# 3_STM32F103_Debugger.net
KiCad netlist of a schematic drawn in Altium Designer
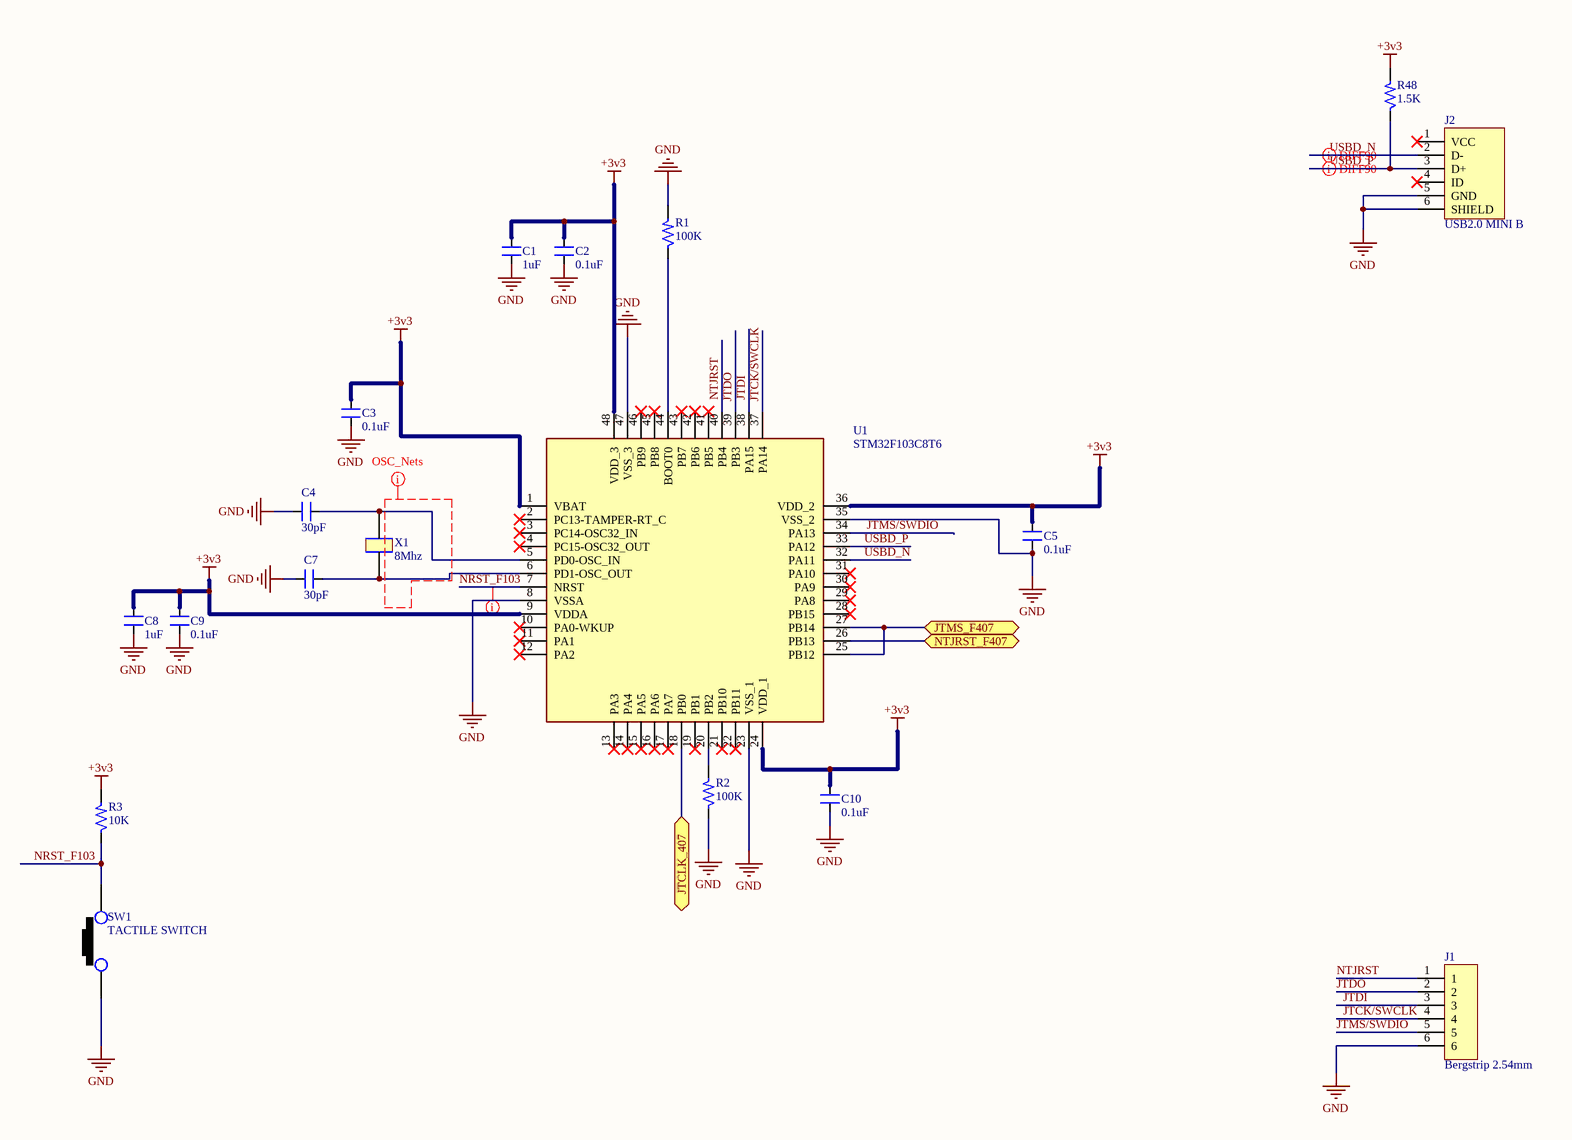
[diagram p0: [3]STM32F103_Debugger.SchDoc]

(export (version "E")
  (design (tool "Eeschema 10.0.6"))
  (components
    (comp (ref "C1")
      (value "1uF")
      (footprint "CAP_0805")
      (description "1µF ±5% 50V Ceramic Capacitor X7R 0805 (2012 Metric)")
      (fields
        (field (name "MANUFACTURER") "Samsung")
        (field (name "MANUFACTURER PART NUMBER") "CC0805JKX7R9BB105")
      )
      (libsource (lib "ESTEEMPCBLIB") (part "CAP_1uF-50V-5%-0805"))
    )
    (comp (ref "C2")
      (value "0.1uF")
      (footprint "CAP_0805")
      (description "0.1µF ±5% 50V Ceramic Capacitor X7R 0805 (2012 Metric)")
      (fields
        (field (name "MANUFACTURER") "AVX Corporation")
        (field (name "MANUFACTURER PART NUMBER") "08055C104JAT4A")
      )
      (libsource (lib "ESTEEMPCBLIB") (part "CAP_0.1uF-50V-5%-0805"))
    )
    (comp (ref "C3")
      (value "0.1uF")
      (footprint "CAP_0805")
      (description "0.1µF ±5% 50V Ceramic Capacitor X7R 0805 (2012 Metric)")
      (fields
        (field (name "MANUFACTURER") "AVX Corporation")
        (field (name "MANUFACTURER PART NUMBER") "08055C104JAT4A")
      )
      (libsource (lib "ESTEEMPCBLIB") (part "CAP_0.1uF-50V-5%-0805"))
    )
    (comp (ref "C4")
      (value "30pF")
      (footprint "CAP_0805")
      (description "±10% 50V Ceramic Capacitor C0G, NP0 0805 (2012 Metric)")
      (fields
        (field (name "MANUFACTURER PART NUMBER") "C0805C300K5GAC7800")
        (field (name "MANUFACTURER") "KEMET")
      )
      (libsource (lib "ESTEEMPCBLIB") (part "CAP_30pF-50V-10%-0805"))
    )
    (comp (ref "C5")
      (value "0.1uF")
      (footprint "CAP_0805")
      (description "0.1µF ±5% 50V Ceramic Capacitor X7R 0805 (2012 Metric)")
      (fields
        (field (name "MANUFACTURER") "AVX Corporation")
        (field (name "MANUFACTURER PART NUMBER") "08055C104JAT4A")
      )
      (libsource (lib "ESTEEMPCBLIB") (part "CAP_0.1uF-50V-5%-0805"))
    )
    (comp (ref "C7")
      (value "30pF")
      (footprint "CAP_0805")
      (description "±10% 50V Ceramic Capacitor C0G, NP0 0805 (2012 Metric)")
      (fields
        (field (name "MANUFACTURER PART NUMBER") "C0805C300K5GAC7800")
        (field (name "MANUFACTURER") "KEMET")
      )
      (libsource (lib "ESTEEMPCBLIB") (part "CAP_30pF-50V-10%-0805"))
    )
    (comp (ref "C8")
      (value "1uF")
      (footprint "CAP_0805")
      (description "1µF ±5% 50V Ceramic Capacitor X7R 0805 (2012 Metric)")
      (fields
        (field (name "MANUFACTURER") "Samsung")
        (field (name "MANUFACTURER PART NUMBER") "CC0805JKX7R9BB105")
      )
      (libsource (lib "ESTEEMPCBLIB") (part "CAP_1uF-50V-5%-0805"))
    )
    (comp (ref "C9")
      (value "0.1uF")
      (footprint "CAP_0805")
      (description "0.1µF ±5% 50V Ceramic Capacitor X7R 0805 (2012 Metric)")
      (fields
        (field (name "MANUFACTURER") "AVX Corporation")
        (field (name "MANUFACTURER PART NUMBER") "08055C104JAT4A")
      )
      (libsource (lib "ESTEEMPCBLIB") (part "CAP_0.1uF-50V-5%-0805"))
    )
    (comp (ref "C10")
      (value "0.1uF")
      (footprint "CAP_0805")
      (description "0.1µF ±5% 50V Ceramic Capacitor X7R 0805 (2012 Metric)")
      (fields
        (field (name "MANUFACTURER") "AVX Corporation")
        (field (name "MANUFACTURER PART NUMBER") "08055C104JAT4A")
      )
      (libsource (lib "ESTEEMPCBLIB") (part "CAP_0.1uF-50V-5%-0805"))
    )
    (comp (ref "J1")
      (value "Bergstrip 2.54mm")
      (footprint "CON6_100_59D78_TH_ST")
      (description "6 Pins, 1 Row 2.54mm Pitch, Straight bergstrip, Female")
      (fields (field (name "MANUFACTURER") "Molex") (field (name "MANUFACTURER PART NUMBER") "22-10-2061"))
      (libsource (lib "ESTEEMPCBLIB") (part "CON-BS-SKT_6X1-100-ST-TH"))
    )
    (comp (ref "J2")
      (value "USB2.0 MINI B")
      (footprint "CON_690-005-299-043")
      (description "USB - mini B USB 2.0 Receptacle Connector 5 Position Surface Mount, Right Angle")
      (fields
        (field (name "MANUFACTURER") "EDAC")
        (field (name "MANUFACTURER PART NUMBER") "690-005-299-043")
      )
      (libsource (lib "ESTEEMPCBLIB") (part "CON_USB2.0-MINIB-SMD"))
    )
    (comp (ref "R1")
      (value "100K")
      (footprint "RES_0805")
      (description "100 kOhms ±1% 0.125W, 1/8W Chip Resistor 0805 (2012 Metric) Automotive AEC-Q200 Thick Film")
      (fields (field (name "MANUFACTURER") "Walsin") (field (name "MANUFACTURER PART NUMBER") "WR08X1003FTL"))
      (libsource (lib "ESTEEMPCBLIB") (part "RES_100K-0.125W-1%-0805"))
    )
    (comp (ref "R2")
      (value "100K")
      (footprint "RES_0805")
      (description "100 kOhms ±1% 0.125W, 1/8W Chip Resistor 0805 (2012 Metric) Automotive AEC-Q200 Thick Film")
      (fields (field (name "MANUFACTURER") "Walsin") (field (name "MANUFACTURER PART NUMBER") "WR08X1003FTL"))
      (libsource (lib "ESTEEMPCBLIB") (part "RES_100K-0.125W-1%-0805"))
    )
    (comp (ref "R3")
      (value "10K")
      (footprint "RES_0805")
      (description "10 kOhms ±1% 0.125W, 1/8W Chip Resistor 0805 (2012 Metric) Automotive AEC-Q200 Thick Film")
      (fields (field (name "MANUFACTURER") "CTS") (field (name "MANUFACTURER PART NUMBER") "WR08X1002FTL"))
      (libsource (lib "ESTEEMPCBLIB") (part "RES_10K-0.125W-1%-0805"))
    )
    (comp (ref "R48")
      (value "1.5K")
      (footprint "RES_0805")
      (description "1.5 kOhms ±1% 0.125W, 1/8W Chip Resistor 0805 (2012 Metric) Thick Film")
      (fields
        (field (name "MANUFACTURER") "TE Connectivity Passive Product")
        (field (name "MANUFACTURER PART NUMBER") "CRG0805F1K5")
      )
      (libsource (lib "ESTEEMPCBLIB") (part "RES_1.5K-0.125W-1%-0805"))
    )
    (comp (ref "SW1")
      (value "TACTILE SWITCH")
      (footprint "SW_342_SMD")
      (description "Tactile Switch SPST-NO Top Actuated Surface Mount")
      (fields
        (field (name "MANUFACTURER") "ITT C&K")
        (field (name "MANUFACTURER PART NUMBER") "RS-282G05A3-SMRT")
      )
      (libsource (lib "ESTEEMPCBLIB") (part "SW1_RS-282G05A3-SMRT-SMD"))
    )
    (comp (ref "U1")
      (value "STM32F103C8T6")
      (footprint "LQFP-48_19.6_393_58X11_SMD")
      (description "ARM® Cortex®-M3 STM32F1 Microcontroller IC 32-Bit 72MHz 64KB (64K x 8) FLASH 48-LQFP (7x7)")
      (fields (field (name "MANUFACTURER") "STMicroelectronics"))
      (libsource (lib "ESTEEMPCBLIB") (part "IC_STM32F103C8T6"))
    )
    (comp (ref "X1")
      (value "8Mhz")
      (footprint "XTAL_314_240X47_SMD")
      (description "8MHz ±30ppm Crystal 32pF 60 Ohms HC-49/US")
      (fields
        (field (name "MANUFACTURER") "Fox Electronics")
        (field (name "MANUFACTURER PART NUMBER") "ECS-80-32-5PX-TR")
      )
      (libsource (lib "ESTEEMPCBLIB") (part "XTAL_8MHZ-ECS-80-32-5PX-SMD"))
    )
  )
  (nets
    (net (code "1") (name "+3v3") (class "Default")
      (node (ref "C1") (pin "1") (pinfunction "1_1") (pintype "passive"))
      (node (ref "C10") (pin "2") (pinfunction "2_2") (pintype "passive"))
      (node (ref "C2") (pin "2") (pinfunction "2_2") (pintype "passive"))
      (node (ref "C3") (pin "2") (pinfunction "2_2") (pintype "passive"))
      (node (ref "C5") (pin "2") (pinfunction "2_2") (pintype "passive"))
      (node (ref "C8") (pin "1") (pinfunction "1_1") (pintype "passive"))
      (node (ref "C9") (pin "2") (pinfunction "2_2") (pintype "passive"))
      (node (ref "R3") (pin "2") (pinfunction "2_2") (pintype "passive"))
      (node (ref "R48") (pin "2") (pinfunction "2_2") (pintype "passive"))
      (node (ref "U1") (pin "1") (pinfunction "VBAT_1") (pintype "passive"))
      (node (ref "U1") (pin "24") (pinfunction "VDD_1_24") (pintype "passive"))
      (node (ref "U1") (pin "36") (pinfunction "VDD_2_36") (pintype "passive"))
      (node (ref "U1") (pin "48") (pinfunction "VDD_3_48") (pintype "passive"))
      (node (ref "U1") (pin "9") (pinfunction "VDDA_9") (pintype "passive"))
    )
    (net (code "2") (name "/JTCK{slash}SWCLK") (class "Default")
      (node (ref "J1") (pin "4") (pinfunction "4_4") (pintype "passive"))
      (node (ref "U1") (pin "37") (pinfunction "PA14_37") (pintype "passive"))
    )
    (net (code "3") (name "/JTCLK_407") (class "Default")
      (node (ref "U1") (pin "18") (pinfunction "PB0_18") (pintype "passive"))
    )
    (net (code "4") (name "/JTDI") (class "Default")
      (node (ref "J1") (pin "3") (pinfunction "3_3") (pintype "passive"))
      (node (ref "U1") (pin "38") (pinfunction "PA15_38") (pintype "passive"))
    )
    (net (code "5") (name "/JTDO") (class "Default")
      (node (ref "J1") (pin "2") (pinfunction "2_2") (pintype "passive"))
      (node (ref "U1") (pin "39") (pinfunction "PB3_39") (pintype "passive"))
    )
    (net (code "6") (name "/JTMS_F407") (class "Default")
      (node (ref "U1") (pin "25") (pinfunction "PB12_25") (pintype "passive"))
      (node (ref "U1") (pin "27") (pinfunction "PB14_27") (pintype "passive"))
    )
    (net (code "7") (name "/JTMS{slash}SWDIO") (class "Default")
      (node (ref "J1") (pin "5") (pinfunction "5_5") (pintype "passive"))
      (node (ref "U1") (pin "34") (pinfunction "PA13_34") (pintype "passive"))
    )
    (net (code "8") (name "/NRST_F103") (class "Default")
      (node (ref "R3") (pin "1") (pinfunction "1_1") (pintype "passive"))
      (node (ref "SW1") (pin "2") (pinfunction "2_2") (pintype "passive"))
      (node (ref "U1") (pin "7") (pinfunction "NRST_7") (pintype "passive"))
    )
    (net (code "9") (name "/NTJRST") (class "Default")
      (node (ref "J1") (pin "1") (pinfunction "1_1") (pintype "passive"))
      (node (ref "U1") (pin "40") (pinfunction "PB4_40") (pintype "passive"))
    )
    (net (code "10") (name "/NTJRST_F407") (class "Default")
      (node (ref "U1") (pin "26") (pinfunction "PB13_26") (pintype "passive"))
    )
    (net (code "11") (name "/USBD_N") (class "Default")
      (node (ref "J2") (pin "2") (pinfunction "D-_2") (pintype "passive"))
      (node (ref "U1") (pin "32") (pinfunction "PA11_32") (pintype "passive"))
    )
    (net (code "12") (name "/USBD_P") (class "Default")
      (node (ref "J2") (pin "3") (pinfunction "D+_3") (pintype "passive"))
      (node (ref "R48") (pin "1") (pinfunction "1_1") (pintype "passive"))
      (node (ref "U1") (pin "33") (pinfunction "PA12_33") (pintype "passive"))
    )
    (net (code "13") (name "GND") (class "Default")
      (node (ref "C1") (pin "2") (pinfunction "2_2") (pintype "passive"))
      (node (ref "C10") (pin "1") (pinfunction "1_1") (pintype "passive"))
      (node (ref "C2") (pin "1") (pinfunction "1_1") (pintype "passive"))
      (node (ref "C3") (pin "1") (pinfunction "1_1") (pintype "passive"))
      (node (ref "C4") (pin "1") (pinfunction "1_1") (pintype "passive"))
      (node (ref "C5") (pin "1") (pinfunction "1_1") (pintype "passive"))
      (node (ref "C7") (pin "1") (pinfunction "1_1") (pintype "passive"))
      (node (ref "C8") (pin "2") (pinfunction "2_2") (pintype "passive"))
      (node (ref "C9") (pin "1") (pinfunction "1_1") (pintype "passive"))
      (node (ref "J1") (pin "6") (pinfunction "6_6") (pintype "passive"))
      (node (ref "J2") (pin "5") (pinfunction "GND_5") (pintype "passive"))
      (node (ref "J2") (pin "6") (pinfunction "SHIELD_6") (pintype "passive"))
      (node (ref "R1") (pin "2") (pinfunction "2_2") (pintype "passive"))
      (node (ref "R2") (pin "1") (pinfunction "1_1") (pintype "passive"))
      (node (ref "SW1") (pin "1") (pinfunction "1_1") (pintype "passive"))
      (node (ref "U1") (pin "23") (pinfunction "VSS_1_23") (pintype "passive"))
      (node (ref "U1") (pin "35") (pinfunction "VSS_2_35") (pintype "passive"))
      (node (ref "U1") (pin "47") (pinfunction "VSS_3_47") (pintype "passive"))
      (node (ref "U1") (pin "8") (pinfunction "VSSA_8") (pintype "passive"))
    )
    (net (code "14") (name "Net-(U1-BOOT0)") (class "Default")
      (node (ref "R1") (pin "1") (pinfunction "1_1") (pintype "passive"))
      (node (ref "U1") (pin "44") (pinfunction "BOOT0_44") (pintype "passive"))
    )
    (net (code "15") (name "Net-(U1-PB2)") (class "Default")
      (node (ref "R2") (pin "2") (pinfunction "2_2") (pintype "passive"))
      (node (ref "U1") (pin "20") (pinfunction "PB2_20") (pintype "passive"))
    )
    (net (code "16") (name "Net-(U1-PD0-OSC_IN)") (class "Default")
      (node (ref "C4") (pin "2") (pinfunction "2_2") (pintype "passive"))
      (node (ref "U1") (pin "5") (pinfunction "PD0-OSC_IN_5") (pintype "passive"))
      (node (ref "X1") (pin "2") (pinfunction "2_2") (pintype "passive"))
    )
    (net (code "17") (name "Net-(U1-PD1-OSC_OUT)") (class "Default")
      (node (ref "C7") (pin "2") (pinfunction "2_2") (pintype "passive"))
      (node (ref "U1") (pin "6") (pinfunction "PD1-OSC_OUT_6") (pintype "passive"))
      (node (ref "X1") (pin "1") (pinfunction "1_1") (pintype "passive"))
    )
    (net (code "18") (name "unconnected-(J2-ID-Pad4)") (class "Default")
      (node (ref "J2") (pin "4") (pinfunction "ID_4") (pintype "passive+no_connect"))
    )
    (net (code "19") (name "unconnected-(J2-VCC-Pad1)") (class "Default")
      (node (ref "J2") (pin "1") (pinfunction "VCC_1") (pintype "passive+no_connect"))
    )
    (net (code "20") (name "unconnected-(U1-PA0-WKUP-Pad10)") (class "Default")
      (node (ref "U1") (pin "10") (pinfunction "PA0-WKUP_10") (pintype "passive+no_connect"))
    )
    (net (code "21") (name "unconnected-(U1-PA1-Pad11)") (class "Default")
      (node (ref "U1") (pin "11") (pinfunction "PA1_11") (pintype "passive+no_connect"))
    )
    (net (code "22") (name "unconnected-(U1-PA2-Pad12)") (class "Default")
      (node (ref "U1") (pin "12") (pinfunction "PA2_12") (pintype "passive+no_connect"))
    )
    (net (code "23") (name "unconnected-(U1-PA3-Pad13)") (class "Default")
      (node (ref "U1") (pin "13") (pinfunction "PA3_13") (pintype "passive+no_connect"))
    )
    (net (code "24") (name "unconnected-(U1-PA4-Pad14)") (class "Default")
      (node (ref "U1") (pin "14") (pinfunction "PA4_14") (pintype "passive+no_connect"))
    )
    (net (code "25") (name "unconnected-(U1-PA5-Pad15)") (class "Default")
      (node (ref "U1") (pin "15") (pinfunction "PA5_15") (pintype "passive+no_connect"))
    )
    (net (code "26") (name "unconnected-(U1-PA6-Pad16)") (class "Default")
      (node (ref "U1") (pin "16") (pinfunction "PA6_16") (pintype "passive+no_connect"))
    )
    (net (code "27") (name "unconnected-(U1-PA7-Pad17)") (class "Default")
      (node (ref "U1") (pin "17") (pinfunction "PA7_17") (pintype "passive+no_connect"))
    )
    (net (code "28") (name "unconnected-(U1-PA8-Pad29)") (class "Default")
      (node (ref "U1") (pin "29") (pinfunction "PA8_29") (pintype "passive+no_connect"))
    )
    (net (code "29") (name "unconnected-(U1-PA9-Pad30)") (class "Default")
      (node (ref "U1") (pin "30") (pinfunction "PA9_30") (pintype "passive+no_connect"))
    )
    (net (code "30") (name "unconnected-(U1-PA10-Pad31)") (class "Default")
      (node (ref "U1") (pin "31") (pinfunction "PA10_31") (pintype "passive+no_connect"))
    )
    (net (code "31") (name "unconnected-(U1-PB1-Pad19)") (class "Default")
      (node (ref "U1") (pin "19") (pinfunction "PB1_19") (pintype "passive+no_connect"))
    )
    (net (code "32") (name "unconnected-(U1-PB5-Pad41)") (class "Default")
      (node (ref "U1") (pin "41") (pinfunction "PB5_41") (pintype "passive+no_connect"))
    )
    (net (code "33") (name "unconnected-(U1-PB6-Pad42)") (class "Default")
      (node (ref "U1") (pin "42") (pinfunction "PB6_42") (pintype "passive+no_connect"))
    )
    (net (code "34") (name "unconnected-(U1-PB7-Pad43)") (class "Default")
      (node (ref "U1") (pin "43") (pinfunction "PB7_43") (pintype "passive+no_connect"))
    )
    (net (code "35") (name "unconnected-(U1-PB8-Pad45)") (class "Default")
      (node (ref "U1") (pin "45") (pinfunction "PB8_45") (pintype "passive+no_connect"))
    )
    (net (code "36") (name "unconnected-(U1-PB9-Pad46)") (class "Default")
      (node (ref "U1") (pin "46") (pinfunction "PB9_46") (pintype "passive+no_connect"))
    )
    (net (code "37") (name "unconnected-(U1-PB10-Pad21)") (class "Default")
      (node (ref "U1") (pin "21") (pinfunction "PB10_21") (pintype "passive+no_connect"))
    )
    (net (code "38") (name "unconnected-(U1-PB11-Pad22)") (class "Default")
      (node (ref "U1") (pin "22") (pinfunction "PB11_22") (pintype "passive+no_connect"))
    )
    (net (code "39") (name "unconnected-(U1-PB15-Pad28)") (class "Default")
      (node (ref "U1") (pin "28") (pinfunction "PB15_28") (pintype "passive+no_connect"))
    )
    (net (code "40") (name "unconnected-(U1-PC13-TAMPER-RT_C-Pad2)") (class "Default")
      (node (ref "U1") (pin "2") (pinfunction "PC13-TAMPER-RT_C_2") (pintype "passive+no_connect"))
    )
    (net (code "41") (name "unconnected-(U1-PC14-OSC32_IN-Pad3)") (class "Default")
      (node (ref "U1") (pin "3") (pinfunction "PC14-OSC32_IN_3") (pintype "passive+no_connect"))
    )
    (net (code "42") (name "unconnected-(U1-PC15-OSC32_OUT-Pad4)") (class "Default")
      (node (ref "U1") (pin "4") (pinfunction "PC15-OSC32_OUT_4") (pintype "passive+no_connect"))
    )
  )
)
